# cansat_wiring_v2.net
KiCad netlist of a schematic drawn in EAGLE
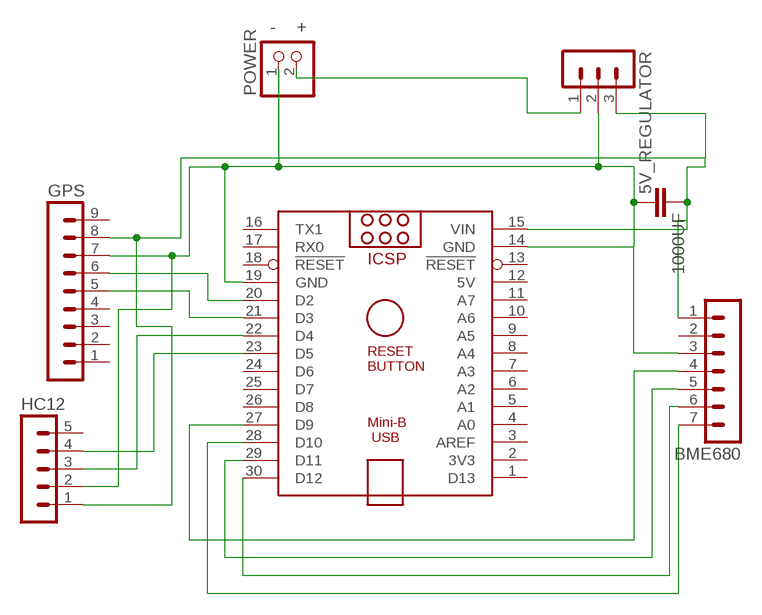
[diagram p0: schematic, sheet 1]

(export (version "E")
  (design (tool "Eeschema 10.0.6"))
  (components
    (comp (ref "5V_REGULATOR")
      (value "MA03-1")
      (footprint "eagle-import:MA03-1")
      (libsource (lib "eagle-import") (part "MA03-1"))
    )
    (comp (ref "1000UF")
      (value "C2.5/2")
      (footprint "eagle-import:C2.5-2")
      (libsource (lib "eagle-import") (part "C2.5/2"))
    )
    (comp (ref "ARDUINO_NANO1")
      (value "ARDUINO_NANO")
      (footprint "eagle-import:ARDUINO_NANO")
      (libsource (lib "eagle-import") (part "ARDUINO_NANO"))
    )
    (comp (ref "BME680")
      (value "MA07-1")
      (footprint "eagle-import:MA07-1")
      (libsource (lib "eagle-import") (part "MA07-1"))
    )
    (comp (ref "GPS")
      (value "MA09-1")
      (footprint "eagle-import:MA09-1")
      (libsource (lib "eagle-import") (part "MA09-1"))
    )
    (comp (ref "HC12")
      (value "MA05-1")
      (footprint "eagle-import:MA05-1")
      (libsource (lib "eagle-import") (part "MA05-1"))
    )
    (comp (ref "POWER")
      (value "PINHD-1X2")
      (footprint "eagle-import:1X02")
      (libsource (lib "eagle-import") (part "PINHD-1X2"))
    )
  )
  (nets
    (net (code "1") (name "/+") (class "Default")
      (node (ref "1000UF") (pin "2") (pinfunction "2_2") (pintype "passive"))
      (node (ref "5V_REGULATOR") (pin "2") (pinfunction "2_2") (pintype "passive"))
      (node (ref "ARDUINO_NANO1") (pin "14") (pinfunction "GND_14") (pintype "power_in"))
      (node (ref "ARDUINO_NANO1") (pin "19") (pinfunction "GND_19") (pintype "power_in"))
      (node (ref "BME680") (pin "3") (pinfunction "3_3") (pintype "passive"))
      (node (ref "GPS") (pin "7") (pinfunction "7_7") (pintype "passive"))
      (node (ref "HC12") (pin "2") (pinfunction "2_2") (pintype "passive"))
      (node (ref "POWER") (pin "1") (pinfunction "1_1") (pintype "passive"))
    )
    (net (code "2") (name "/-") (class "Default")
      (node (ref "5V_REGULATOR") (pin "1") (pinfunction "1_1") (pintype "passive"))
      (node (ref "POWER") (pin "2") (pinfunction "2_2") (pintype "passive"))
    )
    (net (code "3") (name "/5V") (class "Default")
      (node (ref "ARDUINO_NANO1") (pin "12") (pinfunction "5V_12") (pintype "power_in"))
    )
    (net (code "4") (name "Net-(ARDUINO_NANO1-D2)") (class "Default")
      (node (ref "ARDUINO_NANO1") (pin "20") (pinfunction "D2_20") (pintype "bidirectional"))
      (node (ref "GPS") (pin "6") (pinfunction "6_6") (pintype "passive"))
    )
    (net (code "5") (name "Net-(ARDUINO_NANO1-D3)") (class "Default")
      (node (ref "ARDUINO_NANO1") (pin "21") (pinfunction "D3_21") (pintype "bidirectional"))
      (node (ref "GPS") (pin "5") (pinfunction "5_5") (pintype "passive"))
    )
    (net (code "6") (name "Net-(ARDUINO_NANO1-D4)") (class "Default")
      (node (ref "ARDUINO_NANO1") (pin "22") (pinfunction "D4_22") (pintype "bidirectional"))
      (node (ref "HC12") (pin "3") (pinfunction "3_3") (pintype "passive"))
    )
    (net (code "7") (name "Net-(ARDUINO_NANO1-D5)") (class "Default")
      (node (ref "ARDUINO_NANO1") (pin "23") (pinfunction "D5_23") (pintype "bidirectional"))
      (node (ref "HC12") (pin "4") (pinfunction "4_4") (pintype "passive"))
    )
    (net (code "8") (name "Net-(ARDUINO_NANO1-D9)") (class "Default")
      (node (ref "ARDUINO_NANO1") (pin "27") (pinfunction "D9_27") (pintype "bidirectional"))
      (node (ref "BME680") (pin "4") (pinfunction "4_4") (pintype "passive"))
    )
    (net (code "9") (name "Net-(ARDUINO_NANO1-D10)") (class "Default")
      (node (ref "ARDUINO_NANO1") (pin "28") (pinfunction "D10_28") (pintype "bidirectional"))
      (node (ref "BME680") (pin "7") (pinfunction "7_7") (pintype "passive"))
    )
    (net (code "10") (name "Net-(ARDUINO_NANO1-D11)") (class "Default")
      (node (ref "ARDUINO_NANO1") (pin "29") (pinfunction "D11_29") (pintype "bidirectional"))
      (node (ref "BME680") (pin "5") (pinfunction "5_5") (pintype "passive"))
    )
    (net (code "11") (name "Net-(ARDUINO_NANO1-D12)") (class "Default")
      (node (ref "ARDUINO_NANO1") (pin "30") (pinfunction "D12_30") (pintype "bidirectional"))
      (node (ref "BME680") (pin "6") (pinfunction "6_6") (pintype "passive"))
    )
    (net (code "12") (name "Net-(ARDUINO_NANO1-VIN)") (class "Default")
      (node (ref "1000UF") (pin "1") (pinfunction "1_1") (pintype "passive"))
      (node (ref "5V_REGULATOR") (pin "3") (pinfunction "3_3") (pintype "passive"))
      (node (ref "ARDUINO_NANO1") (pin "15") (pinfunction "VIN_15") (pintype "power_in"))
      (node (ref "BME680") (pin "1") (pinfunction "1_1") (pintype "passive"))
      (node (ref "GPS") (pin "8") (pinfunction "8_8") (pintype "passive"))
      (node (ref "HC12") (pin "1") (pinfunction "1_1") (pintype "passive"))
    )
    (net (code "13") (name "unconnected-(ARDUINO_NANO1-3V3-Pad2)") (class "Default")
      (node (ref "ARDUINO_NANO1") (pin "2") (pinfunction "3V3_2") (pintype "output"))
    )
    (net (code "14") (name "unconnected-(ARDUINO_NANO1-A0-Pad4)") (class "Default")
      (node (ref "ARDUINO_NANO1") (pin "4") (pinfunction "A0_4") (pintype "bidirectional"))
    )
    (net (code "15") (name "unconnected-(ARDUINO_NANO1-A1-Pad5)") (class "Default")
      (node (ref "ARDUINO_NANO1") (pin "5") (pinfunction "A1_5") (pintype "bidirectional"))
    )
    (net (code "16") (name "unconnected-(ARDUINO_NANO1-A2-Pad6)") (class "Default")
      (node (ref "ARDUINO_NANO1") (pin "6") (pinfunction "A2_6") (pintype "bidirectional"))
    )
    (net (code "17") (name "unconnected-(ARDUINO_NANO1-A3-Pad7)") (class "Default")
      (node (ref "ARDUINO_NANO1") (pin "7") (pinfunction "A3_7") (pintype "bidirectional"))
    )
    (net (code "18") (name "unconnected-(ARDUINO_NANO1-A4-Pad8)") (class "Default")
      (node (ref "ARDUINO_NANO1") (pin "8") (pinfunction "A4_8") (pintype "bidirectional"))
    )
    (net (code "19") (name "unconnected-(ARDUINO_NANO1-A5-Pad9)") (class "Default")
      (node (ref "ARDUINO_NANO1") (pin "9") (pinfunction "A5_9") (pintype "bidirectional"))
    )
    (net (code "20") (name "unconnected-(ARDUINO_NANO1-A6-Pad10)") (class "Default")
      (node (ref "ARDUINO_NANO1") (pin "10") (pinfunction "A6_10") (pintype "bidirectional"))
    )
    (net (code "21") (name "unconnected-(ARDUINO_NANO1-A7-Pad11)") (class "Default")
      (node (ref "ARDUINO_NANO1") (pin "11") (pinfunction "A7_11") (pintype "bidirectional"))
    )
    (net (code "22") (name "unconnected-(ARDUINO_NANO1-AREF-Pad3)") (class "Default")
      (node (ref "ARDUINO_NANO1") (pin "3") (pinfunction "AREF_3") (pintype "input"))
    )
    (net (code "23") (name "unconnected-(ARDUINO_NANO1-D6-Pad24)") (class "Default")
      (node (ref "ARDUINO_NANO1") (pin "24") (pinfunction "D6_24") (pintype "bidirectional"))
    )
    (net (code "24") (name "unconnected-(ARDUINO_NANO1-D7-Pad25)") (class "Default")
      (node (ref "ARDUINO_NANO1") (pin "25") (pinfunction "D7_25") (pintype "bidirectional"))
    )
    (net (code "25") (name "unconnected-(ARDUINO_NANO1-D8-Pad26)") (class "Default")
      (node (ref "ARDUINO_NANO1") (pin "26") (pinfunction "D8_26") (pintype "bidirectional"))
    )
    (net (code "26") (name "unconnected-(ARDUINO_NANO1-D13-Pad1)") (class "Default")
      (node (ref "ARDUINO_NANO1") (pin "1") (pinfunction "D13_1") (pintype "bidirectional"))
    )
    (net (code "27") (name "unconnected-(ARDUINO_NANO1-RX0-Pad17)") (class "Default")
      (node (ref "ARDUINO_NANO1") (pin "17") (pinfunction "RX0_17") (pintype "bidirectional"))
    )
    (net (code "28") (name "unconnected-(ARDUINO_NANO1-TX1-Pad16)") (class "Default")
      (node (ref "ARDUINO_NANO1") (pin "16") (pinfunction "TX1_16") (pintype "bidirectional"))
    )
    (net (code "29") (name "unconnected-(ARDUINO_NANO1-~{RESET}-Pad13)") (class "Default")
      (node (ref "ARDUINO_NANO1") (pin "13") (pinfunction "~{RESET}_13") (pintype "input"))
    )
    (net (code "30") (name "unconnected-(ARDUINO_NANO1-~{RESET}-Pad18)") (class "Default")
      (node (ref "ARDUINO_NANO1") (pin "18") (pinfunction "~{RESET}_18") (pintype "input"))
    )
    (net (code "31") (name "unconnected-(BME680-Pad2)") (class "Default")
      (node (ref "BME680") (pin "2") (pinfunction "2_2") (pintype "passive"))
    )
    (net (code "32") (name "unconnected-(GPS-Pad1)") (class "Default")
      (node (ref "GPS") (pin "1") (pinfunction "1_1") (pintype "passive"))
    )
    (net (code "33") (name "unconnected-(GPS-Pad2)") (class "Default")
      (node (ref "GPS") (pin "2") (pinfunction "2_2") (pintype "passive"))
    )
    (net (code "34") (name "unconnected-(GPS-Pad3)") (class "Default")
      (node (ref "GPS") (pin "3") (pinfunction "3_3") (pintype "passive"))
    )
    (net (code "35") (name "unconnected-(GPS-Pad4)") (class "Default")
      (node (ref "GPS") (pin "4") (pinfunction "4_4") (pintype "passive"))
    )
    (net (code "36") (name "unconnected-(GPS-Pad9)") (class "Default")
      (node (ref "GPS") (pin "9") (pinfunction "9_9") (pintype "passive"))
    )
    (net (code "37") (name "unconnected-(HC12-Pad5)") (class "Default")
      (node (ref "HC12") (pin "5") (pinfunction "5_5") (pintype "passive"))
    )
  )
)
